# qnode8.net
KiCad netlist of a schematic drawn in EAGLE
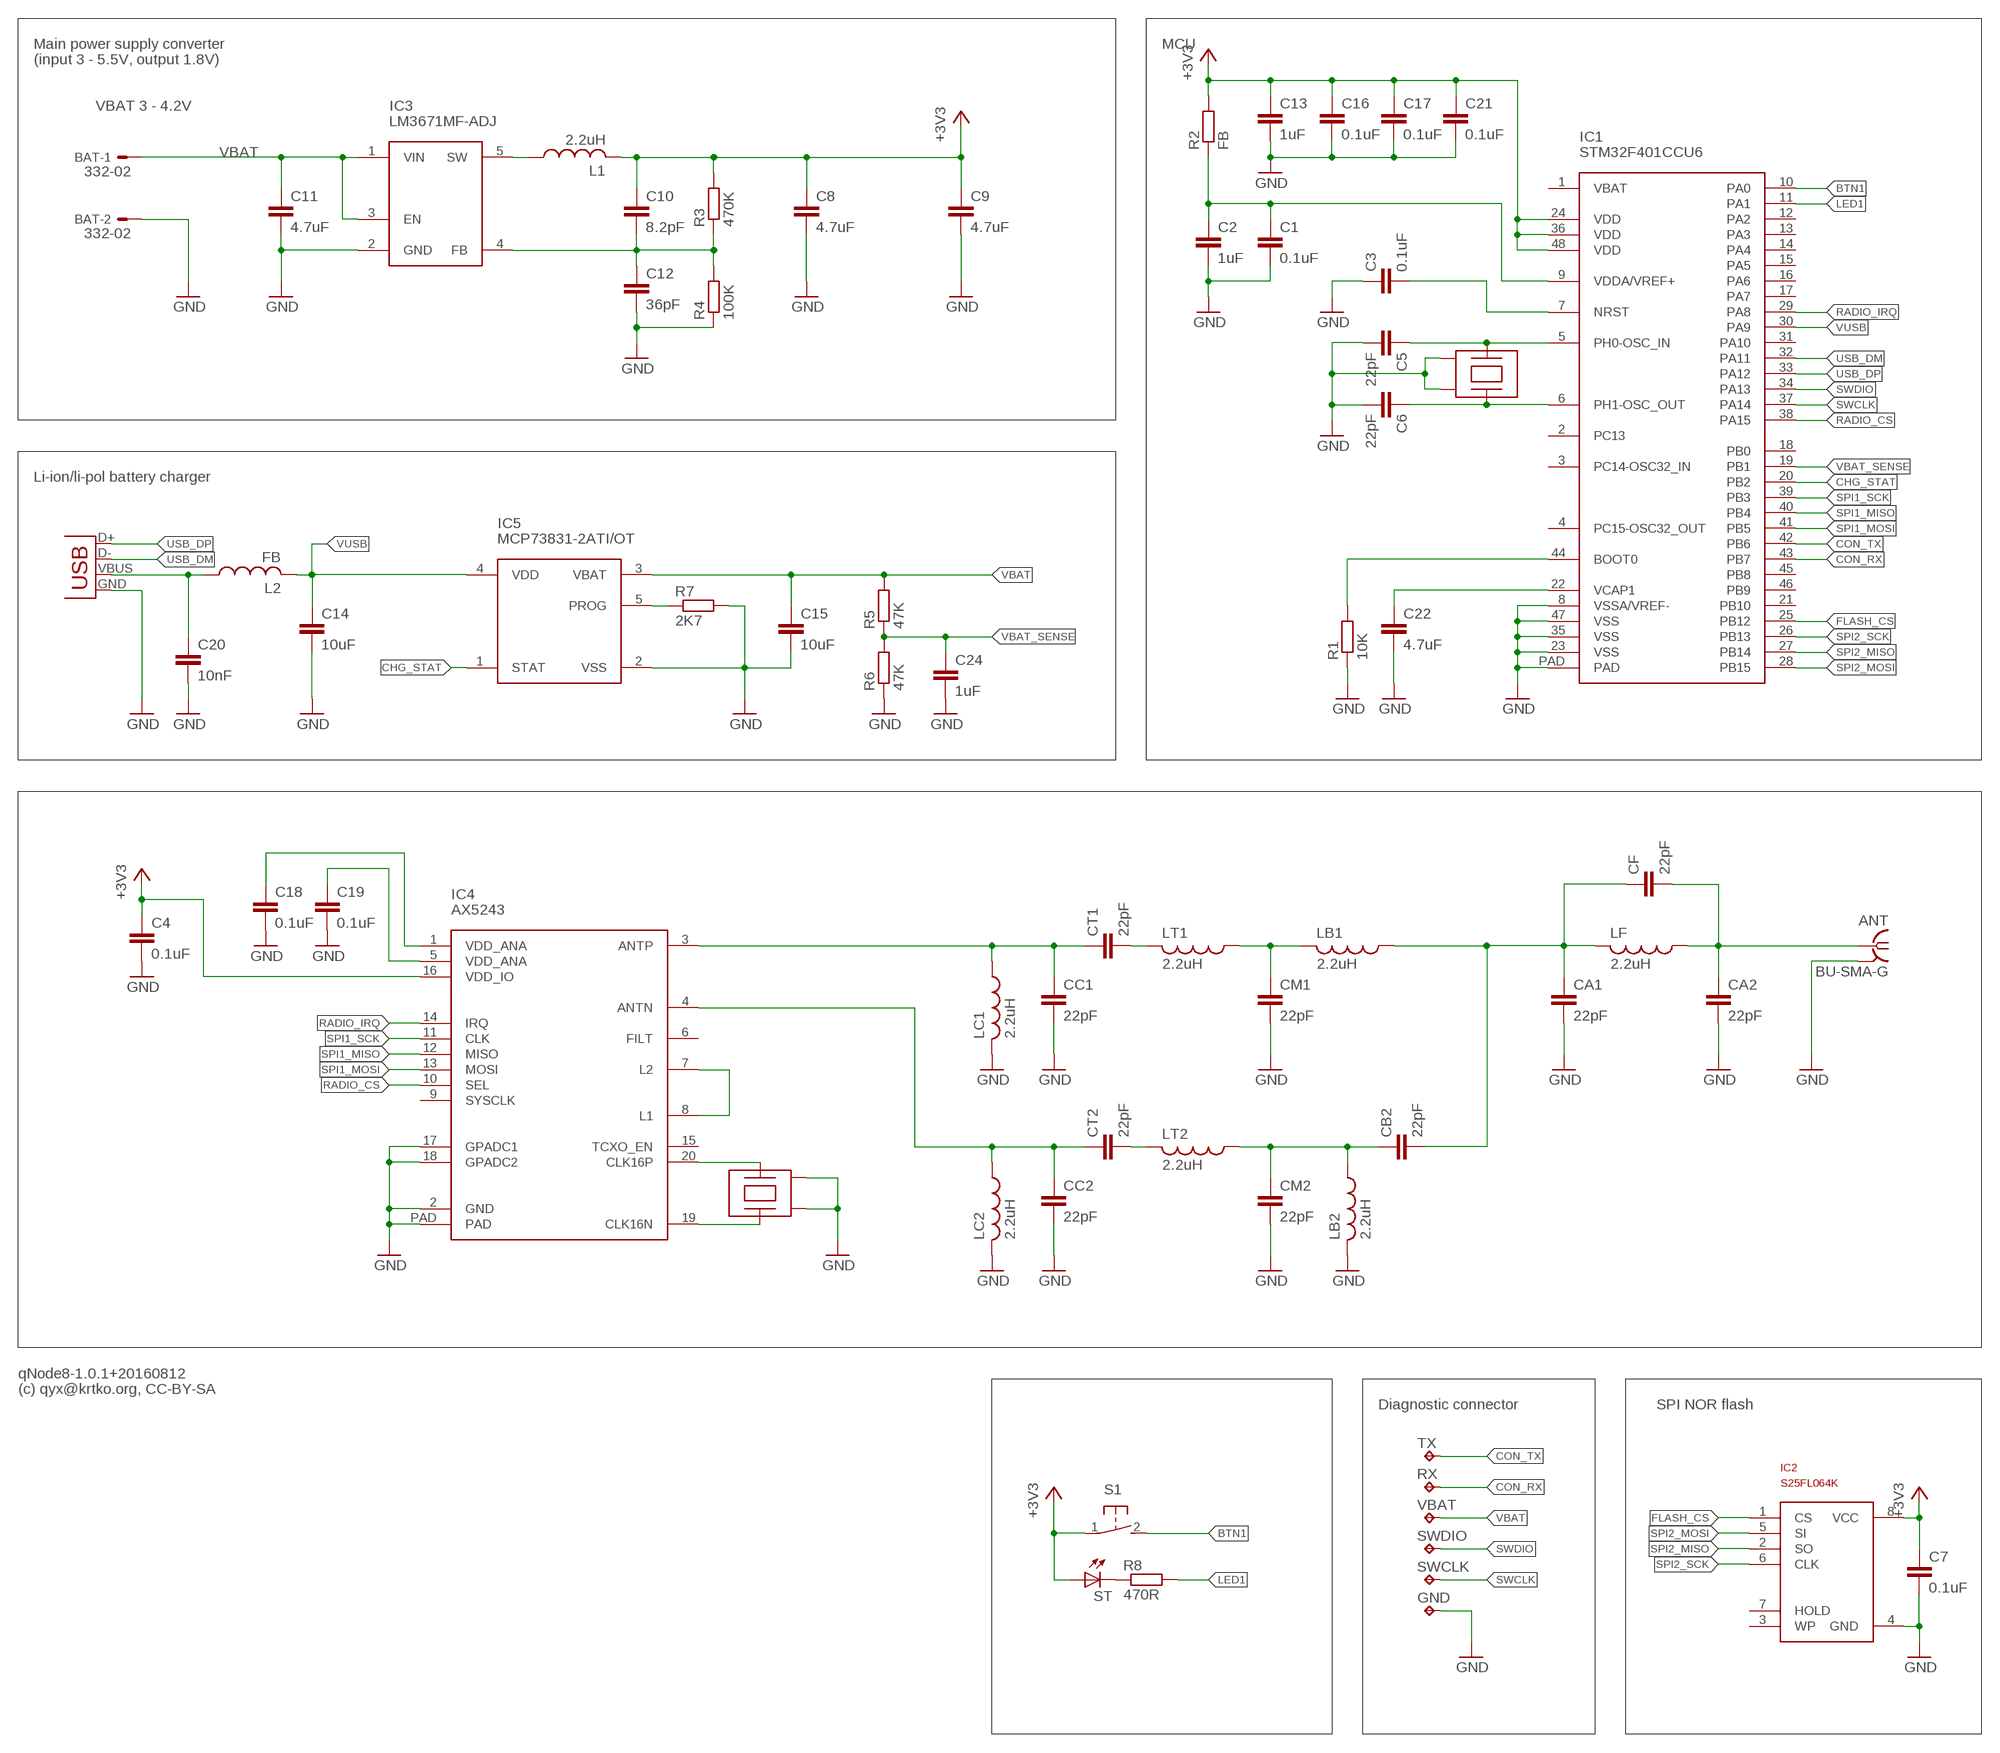
[diagram p0: schematic, sheet 1]

(export (version "E")
  (design (tool "Eeschema 10.0.6"))
  (components
    (comp (ref "ANT")
      (value "BU-SMA-G")
      (footprint "eagle-import:BU-SMA-G")
      (libsource (lib "eagle-import") (part "BU-SMA-G"))
    )
    (comp (ref "BAT")
      (value "332-02")
      (footprint "eagle-import:332-02")
      (libsource (lib "eagle-import") (part "332-02"))
    )
    (comp (ref "C1")
      (value "0.1uF")
      (footprint "eagle-import:C0603")
      (libsource (lib "eagle-import") (part "C-EUC0603"))
    )
    (comp (ref "C2")
      (value "1uF")
      (footprint "eagle-import:C0603")
      (libsource (lib "eagle-import") (part "C-EUC0603"))
    )
    (comp (ref "C3")
      (value "0.1uF")
      (footprint "eagle-import:C0603")
      (libsource (lib "eagle-import") (part "C-EUC0603"))
    )
    (comp (ref "C4")
      (value "0.1uF")
      (footprint "eagle-import:C0603")
      (libsource (lib "eagle-import") (part "C-EUC0603"))
    )
    (comp (ref "C5")
      (value "22pF")
      (footprint "eagle-import:C0603")
      (libsource (lib "eagle-import") (part "C-EUC0603"))
    )
    (comp (ref "C6")
      (value "22pF")
      (footprint "eagle-import:C0603")
      (libsource (lib "eagle-import") (part "C-EUC0603"))
    )
    (comp (ref "C7")
      (value "0.1uF")
      (footprint "eagle-import:C0603")
      (libsource (lib "eagle-import") (part "C-EUC0603"))
    )
    (comp (ref "C8")
      (value "4.7uF")
      (footprint "eagle-import:C0805")
      (libsource (lib "eagle-import") (part "C-EUC0805"))
    )
    (comp (ref "C9")
      (value "4.7uF")
      (footprint "eagle-import:C0805")
      (libsource (lib "eagle-import") (part "C-EUC0805"))
    )
    (comp (ref "C10")
      (value "8.2pF")
      (footprint "eagle-import:C0603")
      (libsource (lib "eagle-import") (part "C-EUC0603"))
    )
    (comp (ref "C11")
      (value "4.7uF")
      (footprint "eagle-import:C0805")
      (libsource (lib "eagle-import") (part "C-EUC0805"))
    )
    (comp (ref "C12")
      (value "36pF")
      (footprint "eagle-import:C0603")
      (libsource (lib "eagle-import") (part "C-EUC0603"))
    )
    (comp (ref "C13")
      (value "1uF")
      (footprint "eagle-import:C0603")
      (libsource (lib "eagle-import") (part "C-EUC0603"))
    )
    (comp (ref "C14")
      (value "10uF")
      (footprint "eagle-import:C1206")
      (libsource (lib "eagle-import") (part "C-EUC1206"))
    )
    (comp (ref "C15")
      (value "10uF")
      (footprint "eagle-import:C1206")
      (libsource (lib "eagle-import") (part "C-EUC1206"))
    )
    (comp (ref "C16")
      (value "0.1uF")
      (footprint "eagle-import:C0603")
      (libsource (lib "eagle-import") (part "C-EUC0603"))
    )
    (comp (ref "C17")
      (value "0.1uF")
      (footprint "eagle-import:C0603")
      (libsource (lib "eagle-import") (part "C-EUC0603"))
    )
    (comp (ref "C18")
      (value "0.1uF")
      (footprint "eagle-import:C0603")
      (libsource (lib "eagle-import") (part "C-EUC0603"))
    )
    (comp (ref "C19")
      (value "0.1uF")
      (footprint "eagle-import:C0603")
      (libsource (lib "eagle-import") (part "C-EUC0603"))
    )
    (comp (ref "C20")
      (value "10nF")
      (footprint "eagle-import:C0603")
      (libsource (lib "eagle-import") (part "C-EUC0603"))
    )
    (comp (ref "C21")
      (value "0.1uF")
      (footprint "eagle-import:C0603")
      (libsource (lib "eagle-import") (part "C-EUC0603"))
    )
    (comp (ref "C22")
      (value "4.7uF")
      (footprint "eagle-import:C0603")
      (libsource (lib "eagle-import") (part "C-EUC0603"))
    )
    (comp (ref "C24")
      (value "1uF")
      (footprint "eagle-import:C0603")
      (libsource (lib "eagle-import") (part "C-EUC0603"))
    )
    (comp (ref "CA1")
      (value "22pF")
      (footprint "eagle-import:C0603")
      (libsource (lib "eagle-import") (part "C-EUC0603"))
    )
    (comp (ref "CA2")
      (value "22pF")
      (footprint "eagle-import:C0603")
      (libsource (lib "eagle-import") (part "C-EUC0603"))
    )
    (comp (ref "CB2")
      (value "22pF")
      (footprint "eagle-import:C0603")
      (libsource (lib "eagle-import") (part "C-EUC0603"))
    )
    (comp (ref "CC1")
      (value "22pF")
      (footprint "eagle-import:C0603")
      (libsource (lib "eagle-import") (part "C-EUC0603"))
    )
    (comp (ref "CC2")
      (value "22pF")
      (footprint "eagle-import:C0603")
      (libsource (lib "eagle-import") (part "C-EUC0603"))
    )
    (comp (ref "CF")
      (value "22pF")
      (footprint "eagle-import:C0603")
      (libsource (lib "eagle-import") (part "C-EUC0603"))
    )
    (comp (ref "CM1")
      (value "22pF")
      (footprint "eagle-import:C0603")
      (libsource (lib "eagle-import") (part "C-EUC0603"))
    )
    (comp (ref "CM2")
      (value "22pF")
      (footprint "eagle-import:C0603")
      (libsource (lib "eagle-import") (part "C-EUC0603"))
    )
    (comp (ref "CT1")
      (value "22pF")
      (footprint "eagle-import:C0603")
      (libsource (lib "eagle-import") (part "C-EUC0603"))
    )
    (comp (ref "CT2")
      (value "22pF")
      (footprint "eagle-import:C0603")
      (libsource (lib "eagle-import") (part "C-EUC0603"))
    )
    (comp (ref "GND")
      (value "TPB2,54")
      (footprint "eagle-import:B2,54")
      (libsource (lib "eagle-import") (part "TPB2,54"))
    )
    (comp (ref "IC1")
      (value "STM32F401CCU6")
      (footprint "eagle-import:UFQFPN48")
      (libsource (lib "eagle-import") (part "STM32F401CCU6"))
    )
    (comp (ref "IC2")
      (value "S25FL064K")
      (footprint "eagle-import:SO-08M")
      (libsource (lib "eagle-import") (part "S25FL064K"))
    )
    (comp (ref "IC3")
      (value "LM3671MF-ADJ")
      (footprint "eagle-import:SOT23-5")
      (libsource (lib "eagle-import") (part "LM3671MF"))
    )
    (comp (ref "IC4")
      (value "AX5243")
      (footprint "eagle-import:QFN20")
      (libsource (lib "eagle-import") (part "AX5243"))
    )
    (comp (ref "IC5")
      (value "MCP73831-2ATI/OT")
      (footprint "eagle-import:SOT23-5")
      (libsource (lib "eagle-import") (part "MCP73831"))
    )
    (comp (ref "L1")
      (value "2.2uH")
      (footprint "eagle-import:L2012C")
      (libsource (lib "eagle-import") (part "L-USL2012C"))
    )
    (comp (ref "L2")
      (value "FB")
      (footprint "eagle-import:L2012C")
      (libsource (lib "eagle-import") (part "L-USL2012C"))
    )
    (comp (ref "LB1")
      (value "2.2uH")
      (footprint "eagle-import:L2012C")
      (libsource (lib "eagle-import") (part "L-USL2012C"))
    )
    (comp (ref "LB2")
      (value "2.2uH")
      (footprint "eagle-import:L2012C")
      (libsource (lib "eagle-import") (part "L-USL2012C"))
    )
    (comp (ref "LC1")
      (value "2.2uH")
      (footprint "eagle-import:L2012C")
      (libsource (lib "eagle-import") (part "L-USL2012C"))
    )
    (comp (ref "LC2")
      (value "2.2uH")
      (footprint "eagle-import:L2012C")
      (libsource (lib "eagle-import") (part "L-USL2012C"))
    )
    (comp (ref "LF")
      (value "2.2uH")
      (footprint "eagle-import:L2012C")
      (libsource (lib "eagle-import") (part "L-USL2012C"))
    )
    (comp (ref "LT1")
      (value "2.2uH")
      (footprint "eagle-import:L2012C")
      (libsource (lib "eagle-import") (part "L-USL2012C"))
    )
    (comp (ref "LT2")
      (value "2.2uH")
      (footprint "eagle-import:L2012C")
      (libsource (lib "eagle-import") (part "L-USL2012C"))
    )
    (comp (ref "R1")
      (value "10K")
      (footprint "eagle-import:R0603")
      (libsource (lib "eagle-import") (part "R-EU_R0603"))
    )
    (comp (ref "R2")
      (value "FB")
      (footprint "eagle-import:R0603")
      (libsource (lib "eagle-import") (part "R-EU_R0603"))
    )
    (comp (ref "R3")
      (value "470K")
      (footprint "eagle-import:R0603")
      (libsource (lib "eagle-import") (part "R-EU_R0603"))
    )
    (comp (ref "R4")
      (value "100K")
      (footprint "eagle-import:R0603")
      (libsource (lib "eagle-import") (part "R-EU_R0603"))
    )
    (comp (ref "R5")
      (value "47K")
      (footprint "eagle-import:R0603")
      (libsource (lib "eagle-import") (part "R-EU_R0603"))
    )
    (comp (ref "R6")
      (value "47K")
      (footprint "eagle-import:R0603")
      (libsource (lib "eagle-import") (part "R-EU_R0603"))
    )
    (comp (ref "R7")
      (value "2K7")
      (footprint "eagle-import:R0603")
      (libsource (lib "eagle-import") (part "R-EU_R0603"))
    )
    (comp (ref "R8")
      (value "470R")
      (footprint "eagle-import:R0603")
      (libsource (lib "eagle-import") (part "R-EU_R0603"))
    )
    (comp (ref "RX")
      (value "TPB2,54")
      (footprint "eagle-import:B2,54")
      (libsource (lib "eagle-import") (part "TPB2,54"))
    )
    (comp (ref "S1")
      (value "31-XX")
      (footprint "eagle-import:B3F-31XX")
      (fields (field (name "MPN") "B3F-3100"))
      (libsource (lib "eagle-import") (part "31-XX"))
    )
    (comp (ref "ST")
      (value "LED3MM")
      (footprint "eagle-import:LED3MM")
      (libsource (lib "eagle-import") (part "LED3MM"))
    )
    (comp (ref "SWCLK")
      (value "TPB2,54")
      (footprint "eagle-import:B2,54")
      (libsource (lib "eagle-import") (part "TPB2,54"))
    )
    (comp (ref "SWDIO")
      (value "TPB2,54")
      (footprint "eagle-import:B2,54")
      (libsource (lib "eagle-import") (part "TPB2,54"))
    )
    (comp (ref "TX")
      (value "TPB2,54")
      (footprint "eagle-import:B2,54")
      (libsource (lib "eagle-import") (part "TPB2,54"))
    )
    (comp (ref "USB")
      (value "USB-MICROB")
      (footprint "eagle-import:USB-MICROB")
      (libsource (lib "eagle-import") (part "USB-MICROB"))
    )
    (comp (ref "VBAT")
      (value "TPB2,54")
      (footprint "eagle-import:B2,54")
      (libsource (lib "eagle-import") (part "TPB2,54"))
    )
    (comp (ref "X1")
      (value "XTAL-7M")
      (footprint "eagle-import:XTAL_7M")
      (libsource (lib "eagle-import") (part "XTAL-7M"))
    )
    (comp (ref "X2")
      (value "XTAL-7M")
      (footprint "eagle-import:XTAL_7M")
      (libsource (lib "eagle-import") (part "XTAL-7M"))
    )
  )
  (nets
    (net (code "1") (name "+3V3") (class "Default")
      (node (ref "C10") (pin "1") (pinfunction "1_1") (pintype "passive"))
      (node (ref "C13") (pin "1") (pinfunction "1_1") (pintype "passive"))
      (node (ref "C16") (pin "1") (pinfunction "1_1") (pintype "passive"))
      (node (ref "C17") (pin "1") (pinfunction "1_1") (pintype "passive"))
      (node (ref "C21") (pin "1") (pinfunction "1_1") (pintype "passive"))
      (node (ref "C4") (pin "1") (pinfunction "1_1") (pintype "passive"))
      (node (ref "C7") (pin "1") (pinfunction "1_1") (pintype "passive"))
      (node (ref "C8") (pin "1") (pinfunction "1_1") (pintype "passive"))
      (node (ref "C9") (pin "1") (pinfunction "1_1") (pintype "passive"))
      (node (ref "IC1") (pin "24") (pinfunction "VDD_24") (pintype "bidirectional"))
      (node (ref "IC1") (pin "36") (pinfunction "VDD_36") (pintype "bidirectional"))
      (node (ref "IC1") (pin "48") (pinfunction "VDD_48") (pintype "bidirectional"))
      (node (ref "IC2") (pin "8") (pinfunction "VCC_8") (pintype "power_in"))
      (node (ref "IC4") (pin "16") (pinfunction "VDD_IO_16") (pintype "bidirectional"))
      (node (ref "L1") (pin "2") (pinfunction "2_2") (pintype "passive"))
      (node (ref "R2") (pin "2") (pinfunction "2_2") (pintype "passive"))
      (node (ref "R3") (pin "2") (pinfunction "2_2") (pintype "passive"))
      (node (ref "S1") (pin "1") (pinfunction "P_1") (pintype "passive"))
      (node (ref "ST") (pin "A") (pinfunction "A_A") (pintype "passive"))
    )
    (net (code "2") (name "BTN1") (class "Default")
      (node (ref "IC1") (pin "10") (pinfunction "PA0_10") (pintype "bidirectional"))
      (node (ref "S1") (pin "2") (pinfunction "S_2") (pintype "passive"))
    )
    (net (code "3") (name "CHG_STAT") (class "Default")
      (node (ref "IC1") (pin "20") (pinfunction "PB2_20") (pintype "bidirectional"))
      (node (ref "IC5") (pin "1") (pinfunction "STAT_1") (pintype "bidirectional"))
    )
    (net (code "4") (name "CON_RX") (class "Default")
      (node (ref "IC1") (pin "43") (pinfunction "PB7_43") (pintype "bidirectional"))
      (node (ref "RX") (pin "TP") (pinfunction "TP_TP") (pintype "input"))
    )
    (net (code "5") (name "CON_TX") (class "Default")
      (node (ref "IC1") (pin "42") (pinfunction "PB6_42") (pintype "bidirectional"))
      (node (ref "TX") (pin "TP") (pinfunction "TP_TP") (pintype "input"))
    )
    (net (code "6") (name "FLASH_CS") (class "Default")
      (node (ref "IC1") (pin "25") (pinfunction "PB12_25") (pintype "bidirectional"))
      (node (ref "IC2") (pin "1") (pinfunction "CS_1") (pintype "bidirectional"))
    )
    (net (code "7") (name "GND") (class "Default")
      (node (ref "ANT") (pin "2") (pinfunction "2_2") (pintype "passive"))
      (node (ref "ANT") (pin "3") (pinfunction "2_3") (pintype "passive"))
      (node (ref "ANT") (pin "4") (pinfunction "2_4") (pintype "passive"))
      (node (ref "ANT") (pin "5") (pinfunction "2_5") (pintype "passive"))
      (node (ref "BAT") (pin "2") (pinfunction "S_2") (pintype "passive"))
      (node (ref "C1") (pin "2") (pinfunction "2_2") (pintype "passive"))
      (node (ref "C11") (pin "2") (pinfunction "2_2") (pintype "passive"))
      (node (ref "C12") (pin "2") (pinfunction "2_2") (pintype "passive"))
      (node (ref "C13") (pin "2") (pinfunction "2_2") (pintype "passive"))
      (node (ref "C14") (pin "2") (pinfunction "2_2") (pintype "passive"))
      (node (ref "C15") (pin "2") (pinfunction "2_2") (pintype "passive"))
      (node (ref "C16") (pin "2") (pinfunction "2_2") (pintype "passive"))
      (node (ref "C17") (pin "2") (pinfunction "2_2") (pintype "passive"))
      (node (ref "C18") (pin "2") (pinfunction "2_2") (pintype "passive"))
      (node (ref "C19") (pin "2") (pinfunction "2_2") (pintype "passive"))
      (node (ref "C2") (pin "2") (pinfunction "2_2") (pintype "passive"))
      (node (ref "C20") (pin "2") (pinfunction "2_2") (pintype "passive"))
      (node (ref "C21") (pin "2") (pinfunction "2_2") (pintype "passive"))
      (node (ref "C22") (pin "2") (pinfunction "2_2") (pintype "passive"))
      (node (ref "C24") (pin "2") (pinfunction "2_2") (pintype "passive"))
      (node (ref "C3") (pin "1") (pinfunction "1_1") (pintype "passive"))
      (node (ref "C4") (pin "2") (pinfunction "2_2") (pintype "passive"))
      (node (ref "C5") (pin "2") (pinfunction "2_2") (pintype "passive"))
      (node (ref "C6") (pin "2") (pinfunction "2_2") (pintype "passive"))
      (node (ref "C7") (pin "2") (pinfunction "2_2") (pintype "passive"))
      (node (ref "C8") (pin "2") (pinfunction "2_2") (pintype "passive"))
      (node (ref "C9") (pin "2") (pinfunction "2_2") (pintype "passive"))
      (node (ref "CA1") (pin "2") (pinfunction "2_2") (pintype "passive"))
      (node (ref "CA2") (pin "2") (pinfunction "2_2") (pintype "passive"))
      (node (ref "CC1") (pin "2") (pinfunction "2_2") (pintype "passive"))
      (node (ref "CC2") (pin "2") (pinfunction "2_2") (pintype "passive"))
      (node (ref "CM1") (pin "2") (pinfunction "2_2") (pintype "passive"))
      (node (ref "CM2") (pin "2") (pinfunction "2_2") (pintype "passive"))
      (node (ref "GND") (pin "TP") (pinfunction "TP_TP") (pintype "input"))
      (node (ref "IC1") (pin "23") (pinfunction "VSS_23") (pintype "bidirectional"))
      (node (ref "IC1") (pin "35") (pinfunction "VSS_35") (pintype "bidirectional"))
      (node (ref "IC1") (pin "47") (pinfunction "VSS_47") (pintype "bidirectional"))
      (node (ref "IC1") (pin "8") (pinfunction "VSSA/VREF-_8") (pintype "bidirectional"))
      (node (ref "IC1") (pin "PAD") (pinfunction "PAD_PAD") (pintype "bidirectional"))
      (node (ref "IC2") (pin "4") (pinfunction "GND_4") (pintype "power_in"))
      (node (ref "IC3") (pin "2") (pinfunction "GND_2") (pintype "bidirectional"))
      (node (ref "IC4") (pin "17") (pinfunction "GPADC1_17") (pintype "bidirectional"))
      (node (ref "IC4") (pin "18") (pinfunction "GPADC2_18") (pintype "bidirectional"))
      (node (ref "IC4") (pin "2") (pinfunction "GND_2") (pintype "bidirectional"))
      (node (ref "IC4") (pin "PAD") (pinfunction "PAD_PAD") (pintype "bidirectional"))
      (node (ref "IC5") (pin "2") (pinfunction "VSS_2") (pintype "bidirectional"))
      (node (ref "LB2") (pin "2") (pinfunction "2_2") (pintype "passive"))
      (node (ref "LC1") (pin "2") (pinfunction "2_2") (pintype "passive"))
      (node (ref "LC2") (pin "2") (pinfunction "2_2") (pintype "passive"))
      (node (ref "R1") (pin "1") (pinfunction "1_1") (pintype "passive"))
      (node (ref "R4") (pin "1") (pinfunction "1_1") (pintype "passive"))
      (node (ref "R6") (pin "1") (pinfunction "1_1") (pintype "passive"))
      (node (ref "R7") (pin "2") (pinfunction "2_2") (pintype "passive"))
      (node (ref "USB") (pin "GND") (pinfunction "GND_GND") (pintype "bidirectional"))
      (node (ref "X1") (pin "2") (pinfunction "G1_2") (pintype "bidirectional"))
      (node (ref "X1") (pin "4") (pinfunction "G2_4") (pintype "bidirectional"))
      (node (ref "X2") (pin "2") (pinfunction "G1_2") (pintype "bidirectional"))
      (node (ref "X2") (pin "4") (pinfunction "G2_4") (pintype "bidirectional"))
    )
    (net (code "8") (name "LED1") (class "Default")
      (node (ref "IC1") (pin "11") (pinfunction "PA1_11") (pintype "bidirectional"))
      (node (ref "R8") (pin "2") (pinfunction "2_2") (pintype "passive"))
    )
    (net (code "9") (name "Net-(ANT-Pad1)") (class "Default")
      (node (ref "ANT") (pin "1") (pinfunction "1_1") (pintype "passive"))
      (node (ref "CA2") (pin "1") (pinfunction "1_1") (pintype "passive"))
      (node (ref "CF") (pin "2") (pinfunction "2_2") (pintype "passive"))
      (node (ref "LF") (pin "1") (pinfunction "1_1") (pintype "passive"))
    )
    (net (code "10") (name "Net-(C18-Pad1)") (class "Default")
      (node (ref "C18") (pin "1") (pinfunction "1_1") (pintype "passive"))
      (node (ref "IC4") (pin "1") (pinfunction "VDD_ANA_1") (pintype "bidirectional"))
    )
    (net (code "11") (name "Net-(C19-Pad1)") (class "Default")
      (node (ref "C19") (pin "1") (pinfunction "1_1") (pintype "passive"))
      (node (ref "IC4") (pin "5") (pinfunction "VDD_ANA_5") (pintype "bidirectional"))
    )
    (net (code "12") (name "Net-(C20-Pad1)") (class "Default")
      (node (ref "C20") (pin "1") (pinfunction "1_1") (pintype "passive"))
      (node (ref "L2") (pin "1") (pinfunction "1_1") (pintype "passive"))
      (node (ref "USB") (pin "VBUS") (pinfunction "VBUS_VBUS") (pintype "bidirectional"))
    )
    (net (code "13") (name "Net-(CA1-Pad1)") (class "Default")
      (node (ref "CA1") (pin "1") (pinfunction "1_1") (pintype "passive"))
      (node (ref "CB2") (pin "2") (pinfunction "2_2") (pintype "passive"))
      (node (ref "CF") (pin "1") (pinfunction "1_1") (pintype "passive"))
      (node (ref "LB1") (pin "1") (pinfunction "1_1") (pintype "passive"))
      (node (ref "LF") (pin "2") (pinfunction "2_2") (pintype "passive"))
    )
    (net (code "14") (name "Net-(CB2-Pad1)") (class "Default")
      (node (ref "CB2") (pin "1") (pinfunction "1_1") (pintype "passive"))
      (node (ref "CM2") (pin "1") (pinfunction "1_1") (pintype "passive"))
      (node (ref "LB2") (pin "1") (pinfunction "1_1") (pintype "passive"))
      (node (ref "LT2") (pin "1") (pinfunction "1_1") (pintype "passive"))
    )
    (net (code "15") (name "Net-(CM1-Pad1)") (class "Default")
      (node (ref "CM1") (pin "1") (pinfunction "1_1") (pintype "passive"))
      (node (ref "LB1") (pin "2") (pinfunction "2_2") (pintype "passive"))
      (node (ref "LT1") (pin "1") (pinfunction "1_1") (pintype "passive"))
    )
    (net (code "16") (name "Net-(CT1-Pad2)") (class "Default")
      (node (ref "CT1") (pin "2") (pinfunction "2_2") (pintype "passive"))
      (node (ref "LT1") (pin "2") (pinfunction "2_2") (pintype "passive"))
    )
    (net (code "17") (name "Net-(CT2-Pad2)") (class "Default")
      (node (ref "CT2") (pin "2") (pinfunction "2_2") (pintype "passive"))
      (node (ref "LT2") (pin "2") (pinfunction "2_2") (pintype "passive"))
    )
    (net (code "18") (name "Net-(IC1-BOOT0)") (class "Default")
      (node (ref "IC1") (pin "44") (pinfunction "BOOT0_44") (pintype "bidirectional"))
      (node (ref "R1") (pin "2") (pinfunction "2_2") (pintype "passive"))
    )
    (net (code "19") (name "Net-(IC1-NRST)") (class "Default")
      (node (ref "C3") (pin "2") (pinfunction "2_2") (pintype "passive"))
      (node (ref "IC1") (pin "7") (pinfunction "NRST_7") (pintype "bidirectional"))
    )
    (net (code "20") (name "Net-(IC1-PH0-OSC_IN)") (class "Default")
      (node (ref "C5") (pin "1") (pinfunction "1_1") (pintype "passive"))
      (node (ref "IC1") (pin "5") (pinfunction "PH0-OSC_IN_5") (pintype "bidirectional"))
      (node (ref "X1") (pin "1") (pinfunction "1_1") (pintype "bidirectional"))
    )
    (net (code "21") (name "Net-(IC1-PH1-OSC_OUT)") (class "Default")
      (node (ref "C6") (pin "1") (pinfunction "1_1") (pintype "passive"))
      (node (ref "IC1") (pin "6") (pinfunction "PH1-OSC_OUT_6") (pintype "bidirectional"))
      (node (ref "X1") (pin "3") (pinfunction "2_3") (pintype "bidirectional"))
    )
    (net (code "22") (name "Net-(IC1-VCAP1)") (class "Default")
      (node (ref "C22") (pin "1") (pinfunction "1_1") (pintype "passive"))
      (node (ref "IC1") (pin "22") (pinfunction "VCAP1_22") (pintype "bidirectional"))
    )
    (net (code "23") (name "Net-(IC1-VDDA{slash}VREF+)") (class "Default")
      (node (ref "C1") (pin "1") (pinfunction "1_1") (pintype "passive"))
      (node (ref "C2") (pin "1") (pinfunction "1_1") (pintype "passive"))
      (node (ref "IC1") (pin "9") (pinfunction "VDDA/VREF+_9") (pintype "bidirectional"))
      (node (ref "R2") (pin "1") (pinfunction "1_1") (pintype "passive"))
    )
    (net (code "24") (name "Net-(IC3-FB)") (class "Default")
      (node (ref "C10") (pin "2") (pinfunction "2_2") (pintype "passive"))
      (node (ref "C12") (pin "1") (pinfunction "1_1") (pintype "passive"))
      (node (ref "IC3") (pin "4") (pinfunction "FB_4") (pintype "bidirectional"))
      (node (ref "R3") (pin "1") (pinfunction "1_1") (pintype "passive"))
      (node (ref "R4") (pin "2") (pinfunction "2_2") (pintype "passive"))
    )
    (net (code "25") (name "Net-(IC3-SW)") (class "Default")
      (node (ref "IC3") (pin "5") (pinfunction "SW_5") (pintype "bidirectional"))
      (node (ref "L1") (pin "1") (pinfunction "1_1") (pintype "passive"))
    )
    (net (code "26") (name "Net-(IC4-ANTN)") (class "Default")
      (node (ref "CC2") (pin "1") (pinfunction "1_1") (pintype "passive"))
      (node (ref "CT2") (pin "1") (pinfunction "1_1") (pintype "passive"))
      (node (ref "IC4") (pin "4") (pinfunction "ANTN_4") (pintype "bidirectional"))
      (node (ref "LC2") (pin "1") (pinfunction "1_1") (pintype "passive"))
    )
    (net (code "27") (name "Net-(IC4-ANTP)") (class "Default")
      (node (ref "CC1") (pin "1") (pinfunction "1_1") (pintype "passive"))
      (node (ref "CT1") (pin "1") (pinfunction "1_1") (pintype "passive"))
      (node (ref "IC4") (pin "3") (pinfunction "ANTP_3") (pintype "bidirectional"))
      (node (ref "LC1") (pin "1") (pinfunction "1_1") (pintype "passive"))
    )
    (net (code "28") (name "Net-(IC4-CLK16N)") (class "Default")
      (node (ref "IC4") (pin "19") (pinfunction "CLK16N_19") (pintype "bidirectional"))
      (node (ref "X2") (pin "3") (pinfunction "2_3") (pintype "bidirectional"))
    )
    (net (code "29") (name "Net-(IC4-CLK16P)") (class "Default")
      (node (ref "IC4") (pin "20") (pinfunction "CLK16P_20") (pintype "bidirectional"))
      (node (ref "X2") (pin "1") (pinfunction "1_1") (pintype "bidirectional"))
    )
    (net (code "30") (name "Net-(IC4-L1)") (class "Default")
      (node (ref "IC4") (pin "7") (pinfunction "L2_7") (pintype "bidirectional"))
      (node (ref "IC4") (pin "8") (pinfunction "L1_8") (pintype "bidirectional"))
    )
    (net (code "31") (name "Net-(IC5-PROG)") (class "Default")
      (node (ref "IC5") (pin "5") (pinfunction "PROG_5") (pintype "bidirectional"))
      (node (ref "R7") (pin "1") (pinfunction "1_1") (pintype "passive"))
    )
    (net (code "32") (name "Net-(ST-C)") (class "Default")
      (node (ref "R8") (pin "1") (pinfunction "1_1") (pintype "passive"))
      (node (ref "ST") (pin "K") (pinfunction "C_K") (pintype "passive"))
    )
    (net (code "33") (name "RADIO_CS") (class "Default")
      (node (ref "IC1") (pin "38") (pinfunction "PA15_38") (pintype "bidirectional"))
      (node (ref "IC4") (pin "10") (pinfunction "SEL_10") (pintype "bidirectional"))
    )
    (net (code "34") (name "RADIO_IRQ") (class "Default")
      (node (ref "IC1") (pin "29") (pinfunction "PA8_29") (pintype "bidirectional"))
      (node (ref "IC4") (pin "14") (pinfunction "IRQ_14") (pintype "bidirectional"))
    )
    (net (code "35") (name "SPI1_MISO") (class "Default")
      (node (ref "IC1") (pin "40") (pinfunction "PB4_40") (pintype "bidirectional"))
      (node (ref "IC4") (pin "12") (pinfunction "MISO_12") (pintype "bidirectional"))
    )
    (net (code "36") (name "SPI1_MOSI") (class "Default")
      (node (ref "IC1") (pin "41") (pinfunction "PB5_41") (pintype "bidirectional"))
      (node (ref "IC4") (pin "13") (pinfunction "MOSI_13") (pintype "bidirectional"))
    )
    (net (code "37") (name "SPI1_SCK") (class "Default")
      (node (ref "IC1") (pin "39") (pinfunction "PB3_39") (pintype "bidirectional"))
      (node (ref "IC4") (pin "11") (pinfunction "CLK_11") (pintype "bidirectional"))
    )
    (net (code "38") (name "SPI2_MISO") (class "Default")
      (node (ref "IC1") (pin "27") (pinfunction "PB14_27") (pintype "bidirectional"))
      (node (ref "IC2") (pin "2") (pinfunction "SO_2") (pintype "bidirectional"))
    )
    (net (code "39") (name "SPI2_MOSI") (class "Default")
      (node (ref "IC1") (pin "28") (pinfunction "PB15_28") (pintype "bidirectional"))
      (node (ref "IC2") (pin "5") (pinfunction "SI_5") (pintype "bidirectional"))
    )
    (net (code "40") (name "SPI2_SCK") (class "Default")
      (node (ref "IC1") (pin "26") (pinfunction "PB13_26") (pintype "bidirectional"))
      (node (ref "IC2") (pin "6") (pinfunction "CLK_6") (pintype "bidirectional"))
    )
    (net (code "41") (name "SWCLK") (class "Default")
      (node (ref "IC1") (pin "37") (pinfunction "PA14_37") (pintype "bidirectional"))
      (node (ref "SWCLK") (pin "TP") (pinfunction "TP_TP") (pintype "input"))
    )
    (net (code "42") (name "SWDIO") (class "Default")
      (node (ref "IC1") (pin "34") (pinfunction "PA13_34") (pintype "bidirectional"))
      (node (ref "SWDIO") (pin "TP") (pinfunction "TP_TP") (pintype "input"))
    )
    (net (code "43") (name "USB_DM") (class "Default")
      (node (ref "IC1") (pin "32") (pinfunction "PA11_32") (pintype "bidirectional"))
      (node (ref "USB") (pin "D-") (pinfunction "D-_D-") (pintype "bidirectional"))
    )
    (net (code "44") (name "USB_DP") (class "Default")
      (node (ref "IC1") (pin "33") (pinfunction "PA12_33") (pintype "bidirectional"))
      (node (ref "USB") (pin "D+") (pinfunction "D+_D+") (pintype "bidirectional"))
    )
    (net (code "45") (name "VBAT") (class "Default")
      (node (ref "BAT") (pin "1") (pinfunction "S_1") (pintype "passive"))
      (node (ref "C11") (pin "1") (pinfunction "1_1") (pintype "passive"))
      (node (ref "C15") (pin "1") (pinfunction "1_1") (pintype "passive"))
      (node (ref "IC3") (pin "1") (pinfunction "VIN_1") (pintype "bidirectional"))
      (node (ref "IC3") (pin "3") (pinfunction "EN_3") (pintype "bidirectional"))
      (node (ref "IC5") (pin "3") (pinfunction "VBAT_3") (pintype "bidirectional"))
      (node (ref "R5") (pin "2") (pinfunction "2_2") (pintype "passive"))
      (node (ref "VBAT") (pin "TP") (pinfunction "TP_TP") (pintype "input"))
    )
    (net (code "46") (name "VBAT_SENSE") (class "Default")
      (node (ref "C24") (pin "1") (pinfunction "1_1") (pintype "passive"))
      (node (ref "IC1") (pin "19") (pinfunction "PB1_19") (pintype "bidirectional"))
      (node (ref "R5") (pin "1") (pinfunction "1_1") (pintype "passive"))
      (node (ref "R6") (pin "2") (pinfunction "2_2") (pintype "passive"))
    )
    (net (code "47") (name "VUSB") (class "Default")
      (node (ref "C14") (pin "1") (pinfunction "1_1") (pintype "passive"))
      (node (ref "IC1") (pin "30") (pinfunction "PA9_30") (pintype "bidirectional"))
      (node (ref "IC5") (pin "4") (pinfunction "VDD_4") (pintype "bidirectional"))
      (node (ref "L2") (pin "2") (pinfunction "2_2") (pintype "passive"))
    )
    (net (code "48") (name "unconnected-(IC1-PA2-Pad12)") (class "Default")
      (node (ref "IC1") (pin "12") (pinfunction "PA2_12") (pintype "bidirectional"))
    )
    (net (code "49") (name "unconnected-(IC1-PA3-Pad13)") (class "Default")
      (node (ref "IC1") (pin "13") (pinfunction "PA3_13") (pintype "bidirectional"))
    )
    (net (code "50") (name "unconnected-(IC1-PA4-Pad14)") (class "Default")
      (node (ref "IC1") (pin "14") (pinfunction "PA4_14") (pintype "bidirectional"))
    )
    (net (code "51") (name "unconnected-(IC1-PA5-Pad15)") (class "Default")
      (node (ref "IC1") (pin "15") (pinfunction "PA5_15") (pintype "bidirectional"))
    )
    (net (code "52") (name "unconnected-(IC1-PA6-Pad16)") (class "Default")
      (node (ref "IC1") (pin "16") (pinfunction "PA6_16") (pintype "bidirectional"))
    )
    (net (code "53") (name "unconnected-(IC1-PA7-Pad17)") (class "Default")
      (node (ref "IC1") (pin "17") (pinfunction "PA7_17") (pintype "bidirectional"))
    )
    (net (code "54") (name "unconnected-(IC1-PA10-Pad31)") (class "Default")
      (node (ref "IC1") (pin "31") (pinfunction "PA10_31") (pintype "bidirectional"))
    )
    (net (code "55") (name "unconnected-(IC1-PB0-Pad18)") (class "Default")
      (node (ref "IC1") (pin "18") (pinfunction "PB0_18") (pintype "bidirectional"))
    )
    (net (code "56") (name "unconnected-(IC1-PB8-Pad45)") (class "Default")
      (node (ref "IC1") (pin "45") (pinfunction "PB8_45") (pintype "bidirectional"))
    )
    (net (code "57") (name "unconnected-(IC1-PB9-Pad46)") (class "Default")
      (node (ref "IC1") (pin "46") (pinfunction "PB9_46") (pintype "bidirectional"))
    )
    (net (code "58") (name "unconnected-(IC1-PB10-Pad21)") (class "Default")
      (node (ref "IC1") (pin "21") (pinfunction "PB10_21") (pintype "bidirectional"))
    )
    (net (code "59") (name "unconnected-(IC1-PC13-Pad2)") (class "Default")
      (node (ref "IC1") (pin "2") (pinfunction "PC13_2") (pintype "bidirectional"))
    )
    (net (code "60") (name "unconnected-(IC1-PC14-OSC32_IN-Pad3)") (class "Default")
      (node (ref "IC1") (pin "3") (pinfunction "PC14-OSC32_IN_3") (pintype "bidirectional"))
    )
    (net (code "61") (name "unconnected-(IC1-PC15-OSC32_OUT-Pad4)") (class "Default")
      (node (ref "IC1") (pin "4") (pinfunction "PC15-OSC32_OUT_4") (pintype "bidirectional"))
    )
    (net (code "62") (name "unconnected-(IC1-VBAT-Pad1)") (class "Default")
      (node (ref "IC1") (pin "1") (pinfunction "VBAT_1") (pintype "bidirectional"))
    )
    (net (code "63") (name "unconnected-(IC2-HOLD-Pad7)") (class "Default")
      (node (ref "IC2") (pin "7") (pinfunction "HOLD_7") (pintype "bidirectional"))
    )
    (net (code "64") (name "unconnected-(IC2-WP-Pad3)") (class "Default")
      (node (ref "IC2") (pin "3") (pinfunction "WP_3") (pintype "bidirectional"))
    )
    (net (code "65") (name "unconnected-(IC4-FILT-Pad6)") (class "Default")
      (node (ref "IC4") (pin "6") (pinfunction "FILT_6") (pintype "bidirectional"))
    )
    (net (code "66") (name "unconnected-(IC4-SYSCLK-Pad9)") (class "Default")
      (node (ref "IC4") (pin "9") (pinfunction "SYSCLK_9") (pintype "bidirectional"))
    )
    (net (code "67") (name "unconnected-(IC4-TCXO_EN-Pad15)") (class "Default")
      (node (ref "IC4") (pin "15") (pinfunction "TCXO_EN_15") (pintype "bidirectional"))
    )
  )
)
